# project_4.net
KiCad netlist of a schematic drawn in Altium Designer
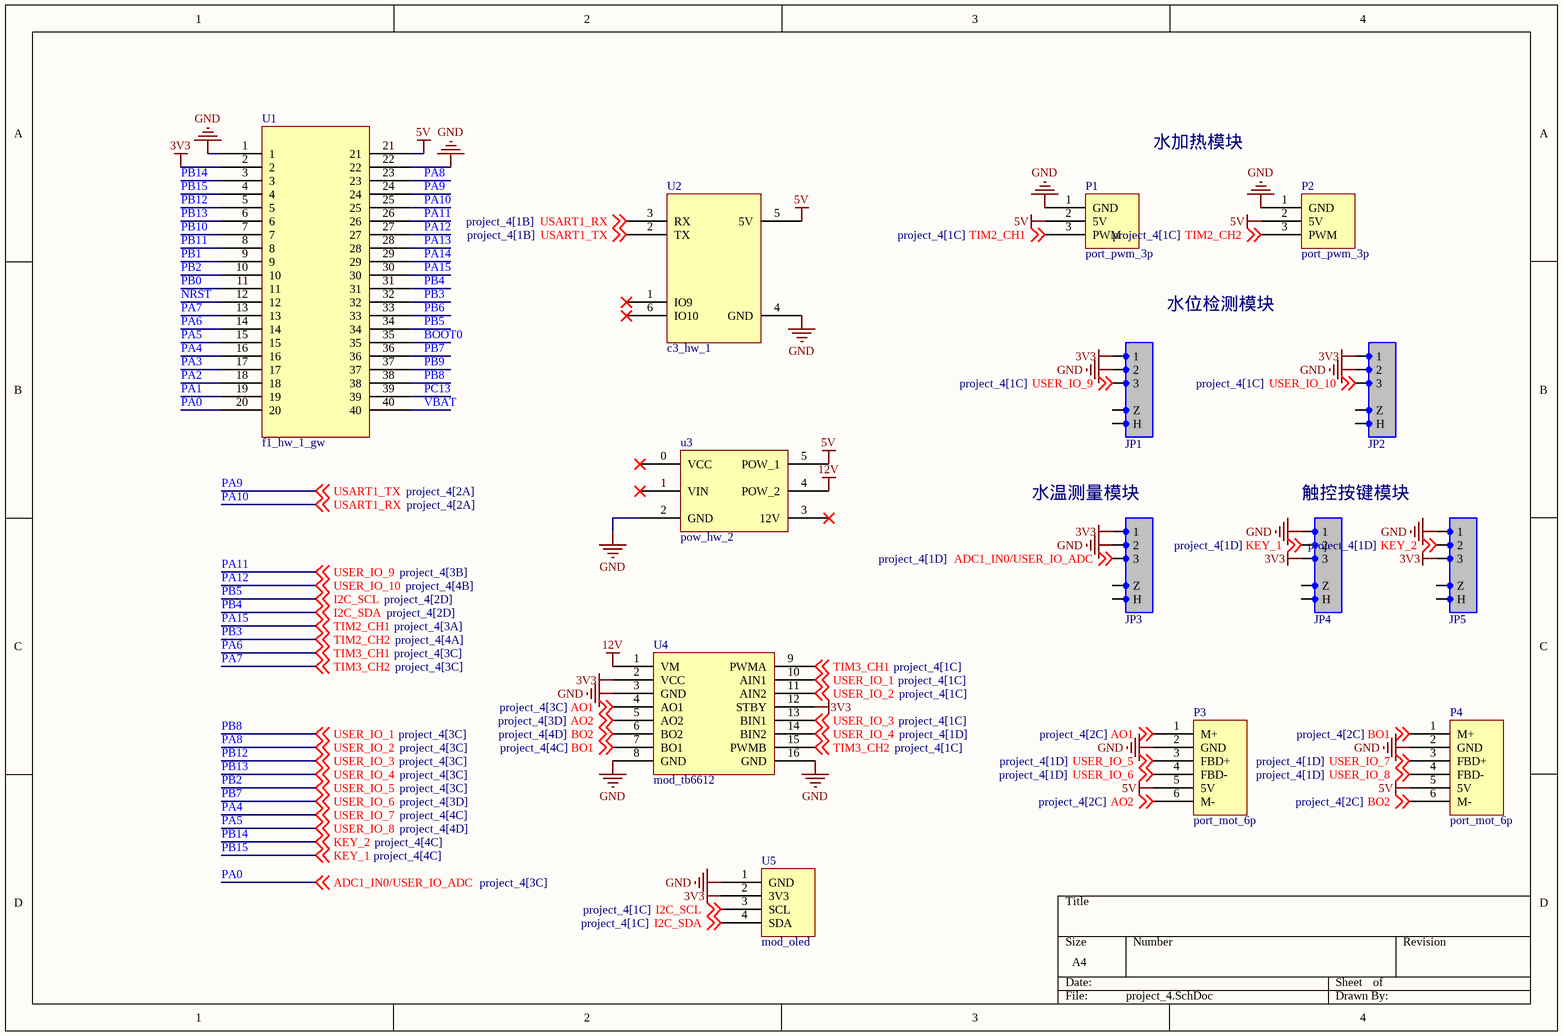
[diagram p0: project_4.SchDoc]

(export (version "E")
  (design (tool "Eeschema 10.0.6"))
  (components
    (comp (ref "JP1")
      (value "HDR-1X3")
      (footprint "XH2.54-WI-3P")
      (description "3P接插件")
      (fields (field (name "版权归属") "源创客"))
      (libsource (lib "14.6-接插件-脚距2.54") (part "Header 3"))
    )
    (comp (ref "JP2")
      (value "HDR-1X3")
      (footprint "XH2.54-WI-3P")
      (description "3P接插件")
      (fields (field (name "版权归属") "源创客"))
      (libsource (lib "14.6-接插件-脚距2.54") (part "Header 3"))
    )
    (comp (ref "JP3")
      (value "HDR-1X3")
      (footprint "XH2.54-WI-3P")
      (description "3P接插件")
      (fields (field (name "版权归属") "源创客"))
      (libsource (lib "14.6-接插件-脚距2.54") (part "Header 3"))
    )
    (comp (ref "JP4")
      (value "HDR-1X3")
      (footprint "HDR2.54-LI-3P")
      (description "3P接插件")
      (fields (field (name "版权归属") "源创客"))
      (libsource (lib "14.6-接插件-脚距2.54") (part "Header 3"))
    )
    (comp (ref "JP5")
      (value "HDR-1X3")
      (footprint "HDR2.54-LI-3P")
      (description "3P接插件")
      (fields (field (name "版权归属") "源创客"))
      (libsource (lib "14.6-接插件-脚距2.54") (part "Header 3"))
    )
    (comp (ref "P1")
      (value "port_pwm_3p")
      (footprint "XH2.54_3P")
      (description "舵机接口\r\nXH2.54弯排针3p")
      (libsource (lib "userLib") (part "port_pwm_3p"))
    )
    (comp (ref "P2")
      (value "port_pwm_3p")
      (footprint "XH2.54_3P")
      (description "舵机接口\r\nXH2.54弯排针3p")
      (libsource (lib "userLib") (part "port_pwm_3p"))
    )
    (comp (ref "P3")
      (value "port_mot_6p")
      (footprint "XH2.54_6P")
      (description "闭环直流电机接口\r\nXH2.54弯排针6p")
      (libsource (lib "userLib") (part "port_mot_6p"))
    )
    (comp (ref "P4")
      (value "port_mot_6p")
      (footprint "XH2.54_6P")
      (description "闭环直流电机接口\r\nXH2.54弯排针6p")
      (libsource (lib "userLib") (part "port_mot_6p"))
    )
    (comp (ref "U1")
      (value "f1_hw_1_gw")
      (footprint "F1_HW_1_GW")
      (libsource (lib "userLib") (part "f1_hw_1_gw"))
    )
    (comp (ref "U2")
      (value "c3_hw_1")
      (footprint "C3_HW_1")
      (description "ESP32C3蓝牙模块\r\n6p排母")
      (libsource (lib "userLib") (part "c3_hw_1"))
    )
    (comp (ref "u3")
      (value "pow_hw_2")
      (footprint "pow_hw_2")
      (description "两路升降压电源模块\r\n6p排母*2")
      (libsource (lib "userLib") (part "pow_hw_2"))
    )
    (comp (ref "U4")
      (value "mod_tb6612")
      (footprint "MOD_TB6612")
      (description "TB6612模块\r\n8p排母*2")
      (libsource (lib "userLib") (part "mod_tb6612"))
    )
    (comp (ref "U5")
      (value "mod_oled")
      (footprint "mod_oled")
      (description "oled模块\r\n4p排母")
      (libsource (lib "userLib") (part "mod_oled"))
    )
  )
  (nets
    (net (code "1") (name "/BOOT0") (class "Default")
      (node (ref "U1") (pin "35") (pinfunction "35_35") (pintype "passive"))
    )
    (net (code "2") (name "/NRST") (class "Default")
      (node (ref "U1") (pin "12") (pinfunction "12_12") (pintype "passive"))
    )
    (net (code "3") (name "/PA1") (class "Default")
      (node (ref "U1") (pin "19") (pinfunction "19_19") (pintype "passive"))
    )
    (net (code "4") (name "/PA2") (class "Default")
      (node (ref "U1") (pin "18") (pinfunction "18_18") (pintype "passive"))
    )
    (net (code "5") (name "/PA3") (class "Default")
      (node (ref "U1") (pin "17") (pinfunction "17_17") (pintype "passive"))
    )
    (net (code "6") (name "/PA13") (class "Default")
      (node (ref "U1") (pin "28") (pinfunction "28_28") (pintype "passive"))
    )
    (net (code "7") (name "/PA14") (class "Default")
      (node (ref "U1") (pin "29") (pinfunction "29_29") (pintype "passive"))
    )
    (net (code "8") (name "/PB0") (class "Default")
      (node (ref "U1") (pin "11") (pinfunction "11_11") (pintype "passive"))
    )
    (net (code "9") (name "/PB1") (class "Default")
      (node (ref "U1") (pin "9") (pinfunction "9_9") (pintype "passive"))
    )
    (net (code "10") (name "/PB6") (class "Default")
      (node (ref "U1") (pin "33") (pinfunction "33_33") (pintype "passive"))
    )
    (net (code "11") (name "/PB9") (class "Default")
      (node (ref "U1") (pin "37") (pinfunction "37_37") (pintype "passive"))
    )
    (net (code "12") (name "/PB10") (class "Default")
      (node (ref "U1") (pin "7") (pinfunction "7_7") (pintype "passive"))
    )
    (net (code "13") (name "/PB11") (class "Default")
      (node (ref "U1") (pin "8") (pinfunction "8_8") (pintype "passive"))
    )
    (net (code "14") (name "/PC13") (class "Default")
      (node (ref "U1") (pin "39") (pinfunction "39_39") (pintype "passive"))
    )
    (net (code "15") (name "/VBAT") (class "Default")
      (node (ref "U1") (pin "40") (pinfunction "40_40") (pintype "passive"))
    )
    (net (code "16") (name "3V3") (class "Default")
      (node (ref "JP1") (pin "1") (pinfunction "1_1") (pintype "passive"))
      (node (ref "JP2") (pin "1") (pinfunction "1_1") (pintype "passive"))
      (node (ref "JP3") (pin "1") (pinfunction "1_1") (pintype "passive"))
      (node (ref "JP4") (pin "3") (pinfunction "3_3") (pintype "passive"))
      (node (ref "JP5") (pin "3") (pinfunction "3_3") (pintype "passive"))
      (node (ref "U1") (pin "2") (pinfunction "2_2") (pintype "passive"))
      (node (ref "U4") (pin "12") (pinfunction "STBY_12") (pintype "passive"))
      (node (ref "U4") (pin "2") (pinfunction "VCC_2") (pintype "passive"))
      (node (ref "U5") (pin "2") (pinfunction "3V3_2") (pintype "passive"))
    )
    (net (code "17") (name "5V") (class "Default")
      (node (ref "P1") (pin "2") (pinfunction "5V_2") (pintype "passive"))
      (node (ref "P2") (pin "2") (pinfunction "5V_2") (pintype "passive"))
      (node (ref "P3") (pin "5") (pinfunction "5V_5") (pintype "passive"))
      (node (ref "P4") (pin "5") (pinfunction "5V_5") (pintype "passive"))
      (node (ref "U1") (pin "21") (pinfunction "21_21") (pintype "passive"))
      (node (ref "U2") (pin "5") (pinfunction "5V_5") (pintype "passive"))
      (node (ref "u3") (pin "5") (pinfunction "POW_1_5") (pintype "passive"))
    )
    (net (code "18") (name "12V") (class "Default")
      (node (ref "U4") (pin "1") (pinfunction "VM_1") (pintype "passive"))
      (node (ref "u3") (pin "4") (pinfunction "POW_2_4") (pintype "passive"))
    )
    (net (code "19") (name "ADC1_IN0{slash}USER_IO_ADC") (class "Default")
      (node (ref "JP3") (pin "3") (pinfunction "3_3") (pintype "passive"))
      (node (ref "U1") (pin "20") (pinfunction "20_20") (pintype "passive"))
    )
    (net (code "20") (name "AO1") (class "Default")
      (node (ref "P3") (pin "1") (pinfunction "M+_1") (pintype "passive"))
      (node (ref "U4") (pin "4") (pinfunction "AO1_4") (pintype "passive"))
    )
    (net (code "21") (name "AO2") (class "Default")
      (node (ref "P3") (pin "6") (pinfunction "M-_6") (pintype "passive"))
      (node (ref "U4") (pin "5") (pinfunction "AO2_5") (pintype "passive"))
    )
    (net (code "22") (name "BO1") (class "Default")
      (node (ref "P4") (pin "1") (pinfunction "M+_1") (pintype "passive"))
      (node (ref "U4") (pin "7") (pinfunction "BO1_7") (pintype "passive"))
    )
    (net (code "23") (name "BO2") (class "Default")
      (node (ref "P4") (pin "6") (pinfunction "M-_6") (pintype "passive"))
      (node (ref "U4") (pin "6") (pinfunction "BO2_6") (pintype "passive"))
    )
    (net (code "24") (name "GND") (class "Default")
      (node (ref "JP1") (pin "2") (pinfunction "2_2") (pintype "passive"))
      (node (ref "JP2") (pin "2") (pinfunction "2_2") (pintype "passive"))
      (node (ref "JP3") (pin "2") (pinfunction "2_2") (pintype "passive"))
      (node (ref "JP4") (pin "1") (pinfunction "1_1") (pintype "passive"))
      (node (ref "JP5") (pin "1") (pinfunction "1_1") (pintype "passive"))
      (node (ref "P1") (pin "1") (pinfunction "GND_1") (pintype "passive"))
      (node (ref "P2") (pin "1") (pinfunction "GND_1") (pintype "passive"))
      (node (ref "P3") (pin "2") (pinfunction "GND_2") (pintype "passive"))
      (node (ref "P4") (pin "2") (pinfunction "GND_2") (pintype "passive"))
      (node (ref "U1") (pin "1") (pinfunction "1_1") (pintype "passive"))
      (node (ref "U1") (pin "22") (pinfunction "22_22") (pintype "passive"))
      (node (ref "U2") (pin "4") (pinfunction "GND_4") (pintype "passive"))
      (node (ref "U4") (pin "16") (pinfunction "GND_16") (pintype "passive"))
      (node (ref "U4") (pin "3") (pinfunction "GND_3") (pintype "passive"))
      (node (ref "U4") (pin "8") (pinfunction "GND_8") (pintype "passive"))
      (node (ref "U5") (pin "1") (pinfunction "GND_1") (pintype "passive"))
      (node (ref "u3") (pin "2") (pinfunction "GND_2") (pintype "passive"))
    )
    (net (code "25") (name "I2C_SCL") (class "Default")
      (node (ref "U1") (pin "34") (pinfunction "34_34") (pintype "passive"))
      (node (ref "U5") (pin "3") (pinfunction "SCL_3") (pintype "passive"))
    )
    (net (code "26") (name "I2C_SDA") (class "Default")
      (node (ref "U1") (pin "31") (pinfunction "31_31") (pintype "passive"))
      (node (ref "U5") (pin "4") (pinfunction "SDA_4") (pintype "passive"))
    )
    (net (code "27") (name "KEY_1") (class "Default")
      (node (ref "JP4") (pin "2") (pinfunction "2_2") (pintype "passive"))
      (node (ref "U1") (pin "4") (pinfunction "4_4") (pintype "passive"))
    )
    (net (code "28") (name "KEY_2") (class "Default")
      (node (ref "JP5") (pin "2") (pinfunction "2_2") (pintype "passive"))
      (node (ref "U1") (pin "3") (pinfunction "3_3") (pintype "passive"))
    )
    (net (code "29") (name "TIM2_CH1") (class "Default")
      (node (ref "P1") (pin "3") (pinfunction "PWM_3") (pintype "passive"))
      (node (ref "U1") (pin "30") (pinfunction "30_30") (pintype "passive"))
    )
    (net (code "30") (name "TIM2_CH2") (class "Default")
      (node (ref "P2") (pin "3") (pinfunction "PWM_3") (pintype "passive"))
      (node (ref "U1") (pin "32") (pinfunction "32_32") (pintype "passive"))
    )
    (net (code "31") (name "TIM3_CH1") (class "Default")
      (node (ref "U1") (pin "14") (pinfunction "14_14") (pintype "passive"))
      (node (ref "U4") (pin "9") (pinfunction "PWMA_9") (pintype "passive"))
    )
    (net (code "32") (name "TIM3_CH2") (class "Default")
      (node (ref "U1") (pin "13") (pinfunction "13_13") (pintype "passive"))
      (node (ref "U4") (pin "15") (pinfunction "PWMB_15") (pintype "passive"))
    )
    (net (code "33") (name "USART1_RX") (class "Default")
      (node (ref "U1") (pin "25") (pinfunction "25_25") (pintype "passive"))
      (node (ref "U2") (pin "3") (pinfunction "RX_3") (pintype "passive"))
    )
    (net (code "34") (name "USART1_TX") (class "Default")
      (node (ref "U1") (pin "24") (pinfunction "24_24") (pintype "passive"))
      (node (ref "U2") (pin "2") (pinfunction "TX_2") (pintype "passive"))
    )
    (net (code "35") (name "USER_IO_1") (class "Default")
      (node (ref "U1") (pin "38") (pinfunction "38_38") (pintype "passive"))
      (node (ref "U4") (pin "10") (pinfunction "AIN1_10") (pintype "passive"))
    )
    (net (code "36") (name "USER_IO_2") (class "Default")
      (node (ref "U1") (pin "23") (pinfunction "23_23") (pintype "passive"))
      (node (ref "U4") (pin "11") (pinfunction "AIN2_11") (pintype "passive"))
    )
    (net (code "37") (name "USER_IO_3") (class "Default")
      (node (ref "U1") (pin "5") (pinfunction "5_5") (pintype "passive"))
      (node (ref "U4") (pin "13") (pinfunction "BIN1_13") (pintype "passive"))
    )
    (net (code "38") (name "USER_IO_4") (class "Default")
      (node (ref "U1") (pin "6") (pinfunction "6_6") (pintype "passive"))
      (node (ref "U4") (pin "14") (pinfunction "BIN2_14") (pintype "passive"))
    )
    (net (code "39") (name "USER_IO_5") (class "Default")
      (node (ref "P3") (pin "3") (pinfunction "FBD+_3") (pintype "passive"))
      (node (ref "U1") (pin "10") (pinfunction "10_10") (pintype "passive"))
    )
    (net (code "40") (name "USER_IO_6") (class "Default")
      (node (ref "P3") (pin "4") (pinfunction "FBD-_4") (pintype "passive"))
      (node (ref "U1") (pin "36") (pinfunction "36_36") (pintype "passive"))
    )
    (net (code "41") (name "USER_IO_7") (class "Default")
      (node (ref "P4") (pin "3") (pinfunction "FBD+_3") (pintype "passive"))
      (node (ref "U1") (pin "16") (pinfunction "16_16") (pintype "passive"))
    )
    (net (code "42") (name "USER_IO_8") (class "Default")
      (node (ref "P4") (pin "4") (pinfunction "FBD-_4") (pintype "passive"))
      (node (ref "U1") (pin "15") (pinfunction "15_15") (pintype "passive"))
    )
    (net (code "43") (name "USER_IO_9") (class "Default")
      (node (ref "JP1") (pin "3") (pinfunction "3_3") (pintype "passive"))
      (node (ref "U1") (pin "26") (pinfunction "26_26") (pintype "passive"))
    )
    (net (code "44") (name "USER_IO_10") (class "Default")
      (node (ref "JP2") (pin "3") (pinfunction "3_3") (pintype "passive"))
      (node (ref "U1") (pin "27") (pinfunction "27_27") (pintype "passive"))
    )
    (net (code "45") (name "unconnected-(JP1-H-Pad100)") (class "Default")
      (node (ref "JP1") (pin "100") (pinfunction "H_100") (pintype "passive"))
    )
    (net (code "46") (name "unconnected-(JP1-Z-Pad0)") (class "Default")
      (node (ref "JP1") (pin "0") (pinfunction "Z_0") (pintype "passive"))
    )
    (net (code "47") (name "unconnected-(JP2-H-Pad100)") (class "Default")
      (node (ref "JP2") (pin "100") (pinfunction "H_100") (pintype "passive"))
    )
    (net (code "48") (name "unconnected-(JP2-Z-Pad0)") (class "Default")
      (node (ref "JP2") (pin "0") (pinfunction "Z_0") (pintype "passive"))
    )
    (net (code "49") (name "unconnected-(JP3-H-Pad100)") (class "Default")
      (node (ref "JP3") (pin "100") (pinfunction "H_100") (pintype "passive"))
    )
    (net (code "50") (name "unconnected-(JP3-Z-Pad0)") (class "Default")
      (node (ref "JP3") (pin "0") (pinfunction "Z_0") (pintype "passive"))
    )
    (net (code "51") (name "unconnected-(JP4-H-Pad100)") (class "Default")
      (node (ref "JP4") (pin "100") (pinfunction "H_100") (pintype "passive"))
    )
    (net (code "52") (name "unconnected-(JP4-Z-Pad0)") (class "Default")
      (node (ref "JP4") (pin "0") (pinfunction "Z_0") (pintype "passive"))
    )
    (net (code "53") (name "unconnected-(JP5-H-Pad100)") (class "Default")
      (node (ref "JP5") (pin "100") (pinfunction "H_100") (pintype "passive"))
    )
    (net (code "54") (name "unconnected-(JP5-Z-Pad0)") (class "Default")
      (node (ref "JP5") (pin "0") (pinfunction "Z_0") (pintype "passive"))
    )
    (net (code "55") (name "unconnected-(U2-IO9-Pad1)") (class "Default")
      (node (ref "U2") (pin "1") (pinfunction "IO9_1") (pintype "passive+no_connect"))
    )
    (net (code "56") (name "unconnected-(U2-IO10-Pad6)") (class "Default")
      (node (ref "U2") (pin "6") (pinfunction "IO10_6") (pintype "passive+no_connect"))
    )
    (net (code "57") (name "unconnected-(u3-12V-Pad3)") (class "Default")
      (node (ref "u3") (pin "3") (pinfunction "12V_3") (pintype "passive+no_connect"))
    )
    (net (code "58") (name "unconnected-(u3-VCC-Pad0)") (class "Default")
      (node (ref "u3") (pin "0") (pinfunction "VCC_0") (pintype "passive+no_connect"))
    )
    (net (code "59") (name "unconnected-(u3-VIN-Pad1)") (class "Default")
      (node (ref "u3") (pin "1") (pinfunction "VIN_1") (pintype "passive+no_connect"))
    )
  )
)
